# QuadWing.net
KiCad netlist of a schematic drawn in EAGLE
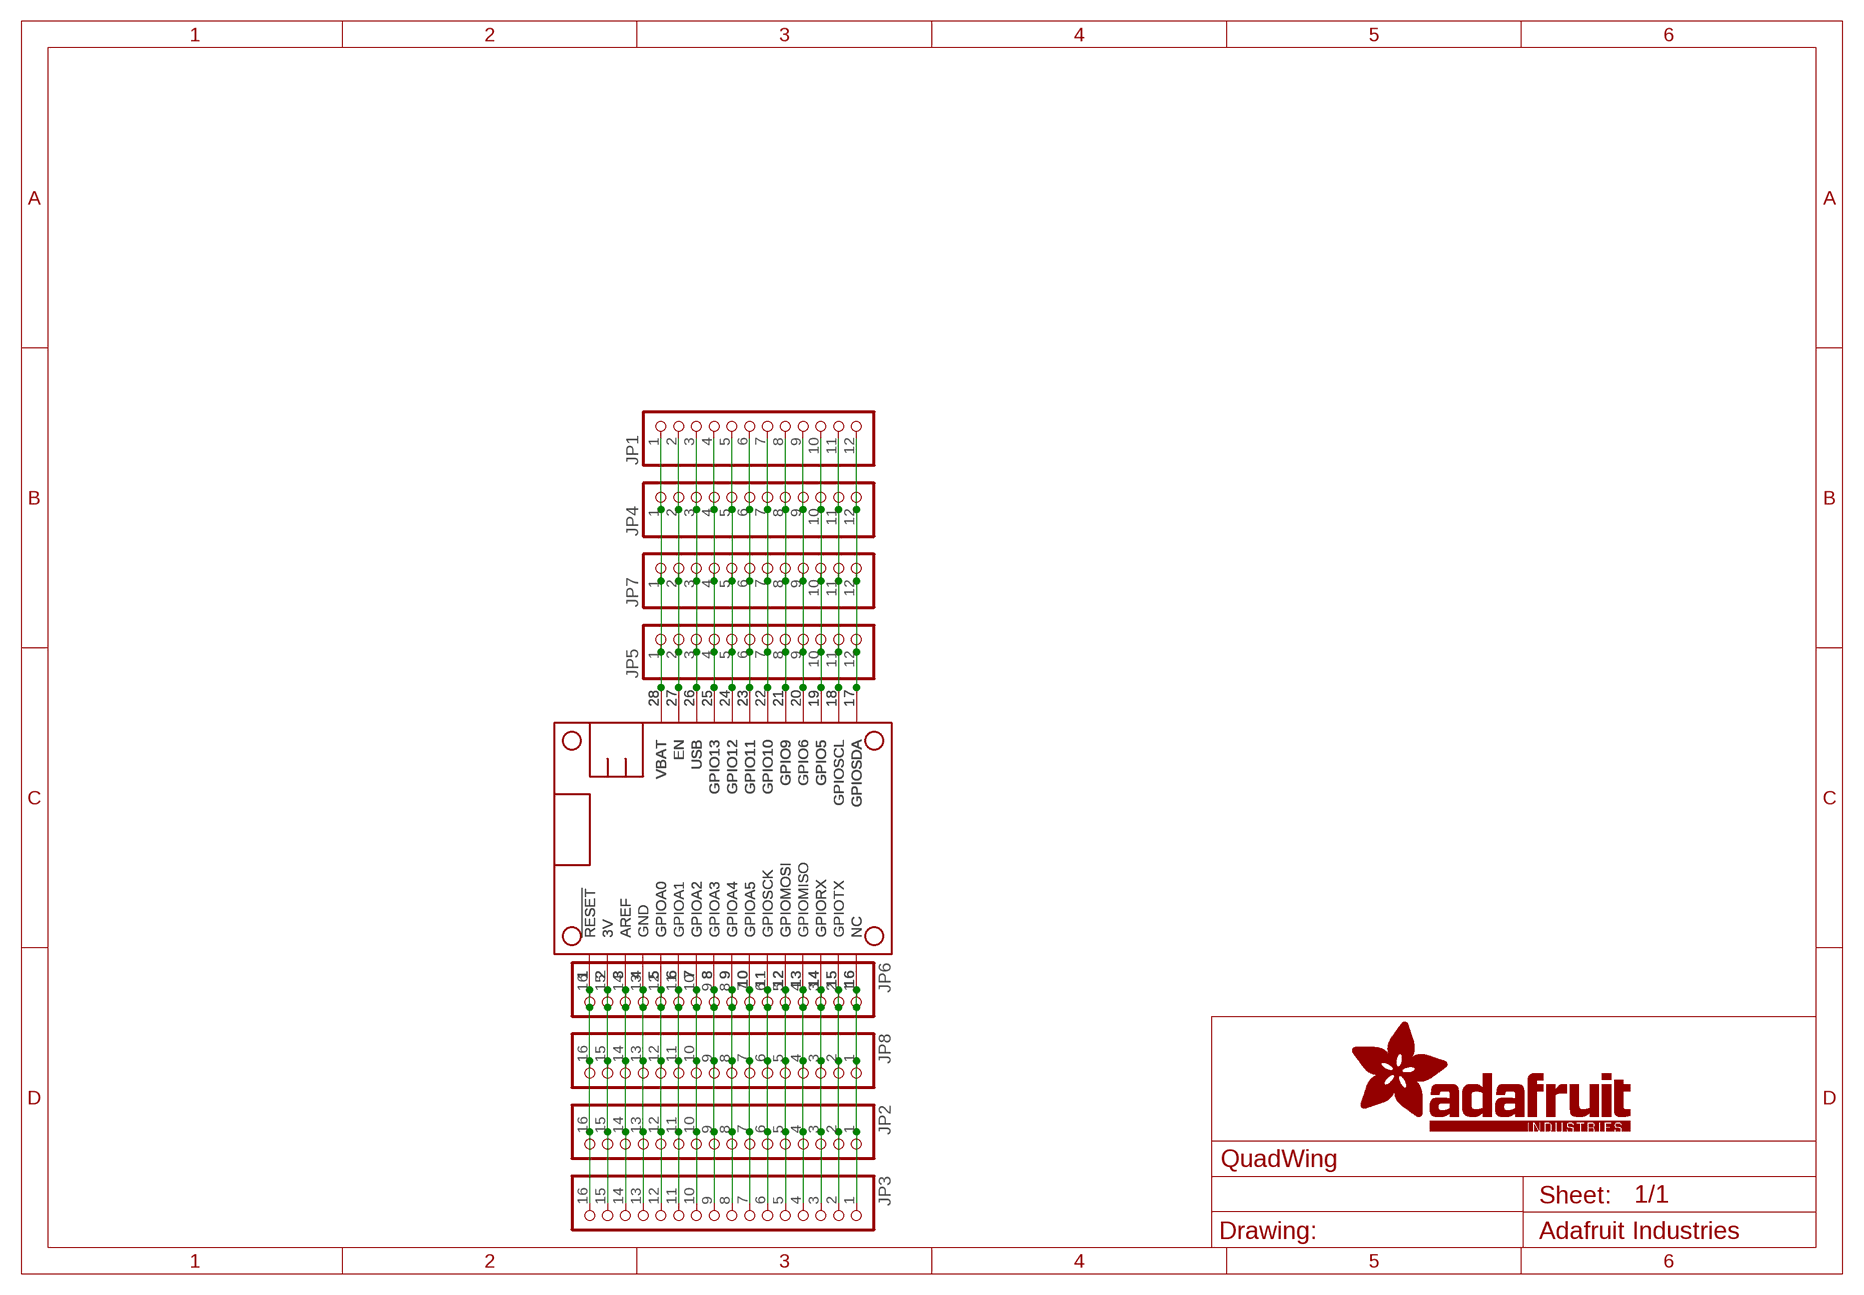
[diagram p0: schematic, sheet 1]

(export (version "E")
  (design (tool "Eeschema 10.0.6"))
  (components
    (comp (ref "JP1")
      (value "HEADER-1X1276MIL")
      (footprint "eagle-import:1X12_ROUND_76MIL")
      (libsource (lib "eagle-import") (part "HEADER-1X1276MIL"))
    )
    (comp (ref "JP2")
      (value "HEADER-1X16_76MIL")
      (footprint "eagle-import:1X16_ROUND_76MIL")
      (libsource (lib "eagle-import") (part "HEADER-1X16_76MIL"))
    )
    (comp (ref "JP3")
      (value "HEADER-1X16_76MIL")
      (footprint "eagle-import:1X16_ROUND_76MIL")
      (libsource (lib "eagle-import") (part "HEADER-1X16_76MIL"))
    )
    (comp (ref "JP4")
      (value "HEADER-1X1276MIL")
      (footprint "eagle-import:1X12_ROUND_76MIL")
      (libsource (lib "eagle-import") (part "HEADER-1X1276MIL"))
    )
    (comp (ref "JP5")
      (value "HEADER-1X1276MIL")
      (footprint "eagle-import:1X12_ROUND_76MIL")
      (libsource (lib "eagle-import") (part "HEADER-1X1276MIL"))
    )
    (comp (ref "JP6")
      (value "HEADER-1X16_76MIL")
      (footprint "eagle-import:1X16_ROUND_76MIL")
      (libsource (lib "eagle-import") (part "HEADER-1X16_76MIL"))
    )
    (comp (ref "JP7")
      (value "HEADER-1X1276MIL")
      (footprint "eagle-import:1X12_ROUND_76MIL")
      (libsource (lib "eagle-import") (part "HEADER-1X1276MIL"))
    )
    (comp (ref "JP8")
      (value "HEADER-1X16_76MIL")
      (footprint "eagle-import:1X16_ROUND_76MIL")
      (libsource (lib "eagle-import") (part "HEADER-1X16_76MIL"))
    )
    (comp (ref "MS1")
      (value "FEATHERWING_NODIM")
      (footprint "eagle-import:FEATHERWING_DIM")
      (libsource (lib "eagle-import") (part "FEATHERWING_NODIM"))
    )
    (comp (ref "MS2")
      (value "FEATHERWING_NODIM")
      (footprint "eagle-import:FEATHERWING_DIM")
      (libsource (lib "eagle-import") (part "FEATHERWING_NODIM"))
    )
    (comp (ref "MS3")
      (value "FEATHERWING_NODIM")
      (footprint "eagle-import:FEATHERWING_DIM")
      (libsource (lib "eagle-import") (part "FEATHERWING_NODIM"))
    )
    (comp (ref "MS4")
      (value "FEATHERWING_NODIM")
      (footprint "eagle-import:FEATHERWING_DIM")
      (libsource (lib "eagle-import") (part "FEATHERWING_NODIM"))
    )
  )
  (nets
    (net (code "1") (name "Net-(MS1-3V)") (class "Default")
      (node (ref "JP2") (pin "15") (pinfunction "15_15") (pintype "passive"))
      (node (ref "JP3") (pin "15") (pinfunction "15_15") (pintype "passive"))
      (node (ref "JP6") (pin "15") (pinfunction "15_15") (pintype "passive"))
      (node (ref "JP8") (pin "15") (pinfunction "15_15") (pintype "passive"))
      (node (ref "MS1") (pin "2") (pinfunction "3V_2") (pintype "power_in"))
      (node (ref "MS2") (pin "2") (pinfunction "3V_2") (pintype "power_in"))
      (node (ref "MS3") (pin "2") (pinfunction "3V_2") (pintype "power_in"))
      (node (ref "MS4") (pin "2") (pinfunction "3V_2") (pintype "power_in"))
    )
    (net (code "2") (name "Net-(MS1-AREF)") (class "Default")
      (node (ref "JP2") (pin "14") (pinfunction "14_14") (pintype "passive"))
      (node (ref "JP3") (pin "14") (pinfunction "14_14") (pintype "passive"))
      (node (ref "JP6") (pin "14") (pinfunction "14_14") (pintype "passive"))
      (node (ref "JP8") (pin "14") (pinfunction "14_14") (pintype "passive"))
      (node (ref "MS1") (pin "3") (pinfunction "AREF_3") (pintype "passive"))
      (node (ref "MS2") (pin "3") (pinfunction "AREF_3") (pintype "passive"))
      (node (ref "MS3") (pin "3") (pinfunction "AREF_3") (pintype "passive"))
      (node (ref "MS4") (pin "3") (pinfunction "AREF_3") (pintype "passive"))
    )
    (net (code "3") (name "Net-(MS1-EN)") (class "Default")
      (node (ref "JP1") (pin "2") (pinfunction "2_2") (pintype "passive"))
      (node (ref "JP4") (pin "2") (pinfunction "2_2") (pintype "passive"))
      (node (ref "JP5") (pin "2") (pinfunction "2_2") (pintype "passive"))
      (node (ref "JP7") (pin "2") (pinfunction "2_2") (pintype "passive"))
      (node (ref "MS1") (pin "27") (pinfunction "EN_27") (pintype "passive"))
      (node (ref "MS2") (pin "27") (pinfunction "EN_27") (pintype "passive"))
      (node (ref "MS3") (pin "27") (pinfunction "EN_27") (pintype "passive"))
      (node (ref "MS4") (pin "27") (pinfunction "EN_27") (pintype "passive"))
    )
    (net (code "4") (name "Net-(MS1-GND)") (class "Default")
      (node (ref "JP2") (pin "13") (pinfunction "13_13") (pintype "passive"))
      (node (ref "JP3") (pin "13") (pinfunction "13_13") (pintype "passive"))
      (node (ref "JP6") (pin "13") (pinfunction "13_13") (pintype "passive"))
      (node (ref "JP8") (pin "13") (pinfunction "13_13") (pintype "passive"))
      (node (ref "MS1") (pin "4") (pinfunction "GND_4") (pintype "power_in"))
      (node (ref "MS2") (pin "4") (pinfunction "GND_4") (pintype "power_in"))
      (node (ref "MS3") (pin "4") (pinfunction "GND_4") (pintype "power_in"))
      (node (ref "MS4") (pin "4") (pinfunction "GND_4") (pintype "power_in"))
    )
    (net (code "5") (name "Net-(MS1-GPIO5)") (class "Default")
      (node (ref "JP1") (pin "10") (pinfunction "10_10") (pintype "passive"))
      (node (ref "JP4") (pin "10") (pinfunction "10_10") (pintype "passive"))
      (node (ref "JP5") (pin "10") (pinfunction "10_10") (pintype "passive"))
      (node (ref "JP7") (pin "10") (pinfunction "10_10") (pintype "passive"))
      (node (ref "MS1") (pin "19") (pinfunction "GPIO5_19") (pintype "bidirectional"))
      (node (ref "MS2") (pin "19") (pinfunction "GPIO5_19") (pintype "bidirectional"))
      (node (ref "MS3") (pin "19") (pinfunction "GPIO5_19") (pintype "bidirectional"))
      (node (ref "MS4") (pin "19") (pinfunction "GPIO5_19") (pintype "bidirectional"))
    )
    (net (code "6") (name "Net-(MS1-GPIO6)") (class "Default")
      (node (ref "JP1") (pin "9") (pinfunction "9_9") (pintype "passive"))
      (node (ref "JP4") (pin "9") (pinfunction "9_9") (pintype "passive"))
      (node (ref "JP5") (pin "9") (pinfunction "9_9") (pintype "passive"))
      (node (ref "JP7") (pin "9") (pinfunction "9_9") (pintype "passive"))
      (node (ref "MS1") (pin "20") (pinfunction "GPIO6_20") (pintype "bidirectional"))
      (node (ref "MS2") (pin "20") (pinfunction "GPIO6_20") (pintype "bidirectional"))
      (node (ref "MS3") (pin "20") (pinfunction "GPIO6_20") (pintype "bidirectional"))
      (node (ref "MS4") (pin "20") (pinfunction "GPIO6_20") (pintype "bidirectional"))
    )
    (net (code "7") (name "Net-(MS1-GPIO9)") (class "Default")
      (node (ref "JP1") (pin "8") (pinfunction "8_8") (pintype "passive"))
      (node (ref "JP4") (pin "8") (pinfunction "8_8") (pintype "passive"))
      (node (ref "JP5") (pin "8") (pinfunction "8_8") (pintype "passive"))
      (node (ref "JP7") (pin "8") (pinfunction "8_8") (pintype "passive"))
      (node (ref "MS1") (pin "21") (pinfunction "GPIO9_21") (pintype "bidirectional"))
      (node (ref "MS2") (pin "21") (pinfunction "GPIO9_21") (pintype "bidirectional"))
      (node (ref "MS3") (pin "21") (pinfunction "GPIO9_21") (pintype "bidirectional"))
      (node (ref "MS4") (pin "21") (pinfunction "GPIO9_21") (pintype "bidirectional"))
    )
    (net (code "8") (name "Net-(MS1-GPIO10)") (class "Default")
      (node (ref "JP1") (pin "7") (pinfunction "7_7") (pintype "passive"))
      (node (ref "JP4") (pin "7") (pinfunction "7_7") (pintype "passive"))
      (node (ref "JP5") (pin "7") (pinfunction "7_7") (pintype "passive"))
      (node (ref "JP7") (pin "7") (pinfunction "7_7") (pintype "passive"))
      (node (ref "MS1") (pin "22") (pinfunction "GPIO10_22") (pintype "bidirectional"))
      (node (ref "MS2") (pin "22") (pinfunction "GPIO10_22") (pintype "bidirectional"))
      (node (ref "MS3") (pin "22") (pinfunction "GPIO10_22") (pintype "bidirectional"))
      (node (ref "MS4") (pin "22") (pinfunction "GPIO10_22") (pintype "bidirectional"))
    )
    (net (code "9") (name "Net-(MS1-GPIO11)") (class "Default")
      (node (ref "JP1") (pin "6") (pinfunction "6_6") (pintype "passive"))
      (node (ref "JP4") (pin "6") (pinfunction "6_6") (pintype "passive"))
      (node (ref "JP5") (pin "6") (pinfunction "6_6") (pintype "passive"))
      (node (ref "JP7") (pin "6") (pinfunction "6_6") (pintype "passive"))
      (node (ref "MS1") (pin "23") (pinfunction "GPIO11_23") (pintype "bidirectional"))
      (node (ref "MS2") (pin "23") (pinfunction "GPIO11_23") (pintype "bidirectional"))
      (node (ref "MS3") (pin "23") (pinfunction "GPIO11_23") (pintype "bidirectional"))
      (node (ref "MS4") (pin "23") (pinfunction "GPIO11_23") (pintype "bidirectional"))
    )
    (net (code "10") (name "Net-(MS1-GPIO12)") (class "Default")
      (node (ref "JP1") (pin "5") (pinfunction "5_5") (pintype "passive"))
      (node (ref "JP4") (pin "5") (pinfunction "5_5") (pintype "passive"))
      (node (ref "JP5") (pin "5") (pinfunction "5_5") (pintype "passive"))
      (node (ref "JP7") (pin "5") (pinfunction "5_5") (pintype "passive"))
      (node (ref "MS1") (pin "24") (pinfunction "GPIO12_24") (pintype "bidirectional"))
      (node (ref "MS2") (pin "24") (pinfunction "GPIO12_24") (pintype "bidirectional"))
      (node (ref "MS3") (pin "24") (pinfunction "GPIO12_24") (pintype "bidirectional"))
      (node (ref "MS4") (pin "24") (pinfunction "GPIO12_24") (pintype "bidirectional"))
    )
    (net (code "11") (name "Net-(MS1-GPIO13)") (class "Default")
      (node (ref "JP1") (pin "4") (pinfunction "4_4") (pintype "passive"))
      (node (ref "JP4") (pin "4") (pinfunction "4_4") (pintype "passive"))
      (node (ref "JP5") (pin "4") (pinfunction "4_4") (pintype "passive"))
      (node (ref "JP7") (pin "4") (pinfunction "4_4") (pintype "passive"))
      (node (ref "MS1") (pin "25") (pinfunction "GPIO13_25") (pintype "bidirectional"))
      (node (ref "MS2") (pin "25") (pinfunction "GPIO13_25") (pintype "bidirectional"))
      (node (ref "MS3") (pin "25") (pinfunction "GPIO13_25") (pintype "bidirectional"))
      (node (ref "MS4") (pin "25") (pinfunction "GPIO13_25") (pintype "bidirectional"))
    )
    (net (code "12") (name "Net-(MS1-GPIOA0)") (class "Default")
      (node (ref "JP2") (pin "12") (pinfunction "12_12") (pintype "passive"))
      (node (ref "JP3") (pin "12") (pinfunction "12_12") (pintype "passive"))
      (node (ref "JP6") (pin "12") (pinfunction "12_12") (pintype "passive"))
      (node (ref "JP8") (pin "12") (pinfunction "12_12") (pintype "passive"))
      (node (ref "MS1") (pin "5") (pinfunction "GPIOA0_5") (pintype "bidirectional"))
      (node (ref "MS2") (pin "5") (pinfunction "GPIOA0_5") (pintype "bidirectional"))
      (node (ref "MS3") (pin "5") (pinfunction "GPIOA0_5") (pintype "bidirectional"))
      (node (ref "MS4") (pin "5") (pinfunction "GPIOA0_5") (pintype "bidirectional"))
    )
    (net (code "13") (name "Net-(MS1-GPIOA1)") (class "Default")
      (node (ref "JP2") (pin "11") (pinfunction "11_11") (pintype "passive"))
      (node (ref "JP3") (pin "11") (pinfunction "11_11") (pintype "passive"))
      (node (ref "JP6") (pin "11") (pinfunction "11_11") (pintype "passive"))
      (node (ref "JP8") (pin "11") (pinfunction "11_11") (pintype "passive"))
      (node (ref "MS1") (pin "6") (pinfunction "GPIOA1_6") (pintype "bidirectional"))
      (node (ref "MS2") (pin "6") (pinfunction "GPIOA1_6") (pintype "bidirectional"))
      (node (ref "MS3") (pin "6") (pinfunction "GPIOA1_6") (pintype "bidirectional"))
      (node (ref "MS4") (pin "6") (pinfunction "GPIOA1_6") (pintype "bidirectional"))
    )
    (net (code "14") (name "Net-(MS1-GPIOA2)") (class "Default")
      (node (ref "JP2") (pin "10") (pinfunction "10_10") (pintype "passive"))
      (node (ref "JP3") (pin "10") (pinfunction "10_10") (pintype "passive"))
      (node (ref "JP6") (pin "10") (pinfunction "10_10") (pintype "passive"))
      (node (ref "JP8") (pin "10") (pinfunction "10_10") (pintype "passive"))
      (node (ref "MS1") (pin "7") (pinfunction "GPIOA2_7") (pintype "bidirectional"))
      (node (ref "MS2") (pin "7") (pinfunction "GPIOA2_7") (pintype "bidirectional"))
      (node (ref "MS3") (pin "7") (pinfunction "GPIOA2_7") (pintype "bidirectional"))
      (node (ref "MS4") (pin "7") (pinfunction "GPIOA2_7") (pintype "bidirectional"))
    )
    (net (code "15") (name "Net-(MS1-GPIOA3)") (class "Default")
      (node (ref "JP2") (pin "9") (pinfunction "9_9") (pintype "passive"))
      (node (ref "JP3") (pin "9") (pinfunction "9_9") (pintype "passive"))
      (node (ref "JP6") (pin "9") (pinfunction "9_9") (pintype "passive"))
      (node (ref "JP8") (pin "9") (pinfunction "9_9") (pintype "passive"))
      (node (ref "MS1") (pin "8") (pinfunction "GPIOA3_8") (pintype "bidirectional"))
      (node (ref "MS2") (pin "8") (pinfunction "GPIOA3_8") (pintype "bidirectional"))
      (node (ref "MS3") (pin "8") (pinfunction "GPIOA3_8") (pintype "bidirectional"))
      (node (ref "MS4") (pin "8") (pinfunction "GPIOA3_8") (pintype "bidirectional"))
    )
    (net (code "16") (name "Net-(MS1-GPIOA4)") (class "Default")
      (node (ref "JP2") (pin "8") (pinfunction "8_8") (pintype "passive"))
      (node (ref "JP3") (pin "8") (pinfunction "8_8") (pintype "passive"))
      (node (ref "JP6") (pin "8") (pinfunction "8_8") (pintype "passive"))
      (node (ref "JP8") (pin "8") (pinfunction "8_8") (pintype "passive"))
      (node (ref "MS1") (pin "9") (pinfunction "GPIOA4_9") (pintype "bidirectional"))
      (node (ref "MS2") (pin "9") (pinfunction "GPIOA4_9") (pintype "bidirectional"))
      (node (ref "MS3") (pin "9") (pinfunction "GPIOA4_9") (pintype "bidirectional"))
      (node (ref "MS4") (pin "9") (pinfunction "GPIOA4_9") (pintype "bidirectional"))
    )
    (net (code "17") (name "Net-(MS1-GPIOA5)") (class "Default")
      (node (ref "JP2") (pin "7") (pinfunction "7_7") (pintype "passive"))
      (node (ref "JP3") (pin "7") (pinfunction "7_7") (pintype "passive"))
      (node (ref "JP6") (pin "7") (pinfunction "7_7") (pintype "passive"))
      (node (ref "JP8") (pin "7") (pinfunction "7_7") (pintype "passive"))
      (node (ref "MS1") (pin "10") (pinfunction "GPIOA5_10") (pintype "bidirectional"))
      (node (ref "MS2") (pin "10") (pinfunction "GPIOA5_10") (pintype "bidirectional"))
      (node (ref "MS3") (pin "10") (pinfunction "GPIOA5_10") (pintype "bidirectional"))
      (node (ref "MS4") (pin "10") (pinfunction "GPIOA5_10") (pintype "bidirectional"))
    )
    (net (code "18") (name "Net-(MS1-GPIOMISO)") (class "Default")
      (node (ref "JP2") (pin "4") (pinfunction "4_4") (pintype "passive"))
      (node (ref "JP3") (pin "4") (pinfunction "4_4") (pintype "passive"))
      (node (ref "JP6") (pin "4") (pinfunction "4_4") (pintype "passive"))
      (node (ref "JP8") (pin "4") (pinfunction "4_4") (pintype "passive"))
      (node (ref "MS1") (pin "13") (pinfunction "GPIOMISO_13") (pintype "bidirectional"))
      (node (ref "MS2") (pin "13") (pinfunction "GPIOMISO_13") (pintype "bidirectional"))
      (node (ref "MS3") (pin "13") (pinfunction "GPIOMISO_13") (pintype "bidirectional"))
      (node (ref "MS4") (pin "13") (pinfunction "GPIOMISO_13") (pintype "bidirectional"))
    )
    (net (code "19") (name "Net-(MS1-GPIOMOSI)") (class "Default")
      (node (ref "JP2") (pin "5") (pinfunction "5_5") (pintype "passive"))
      (node (ref "JP3") (pin "5") (pinfunction "5_5") (pintype "passive"))
      (node (ref "JP6") (pin "5") (pinfunction "5_5") (pintype "passive"))
      (node (ref "JP8") (pin "5") (pinfunction "5_5") (pintype "passive"))
      (node (ref "MS1") (pin "12") (pinfunction "GPIOMOSI_12") (pintype "bidirectional"))
      (node (ref "MS2") (pin "12") (pinfunction "GPIOMOSI_12") (pintype "bidirectional"))
      (node (ref "MS3") (pin "12") (pinfunction "GPIOMOSI_12") (pintype "bidirectional"))
      (node (ref "MS4") (pin "12") (pinfunction "GPIOMOSI_12") (pintype "bidirectional"))
    )
    (net (code "20") (name "Net-(MS1-GPIORX)") (class "Default")
      (node (ref "JP2") (pin "3") (pinfunction "3_3") (pintype "passive"))
      (node (ref "JP3") (pin "3") (pinfunction "3_3") (pintype "passive"))
      (node (ref "JP6") (pin "3") (pinfunction "3_3") (pintype "passive"))
      (node (ref "JP8") (pin "3") (pinfunction "3_3") (pintype "passive"))
      (node (ref "MS1") (pin "14") (pinfunction "GPIORX_14") (pintype "bidirectional"))
      (node (ref "MS2") (pin "14") (pinfunction "GPIORX_14") (pintype "bidirectional"))
      (node (ref "MS3") (pin "14") (pinfunction "GPIORX_14") (pintype "bidirectional"))
      (node (ref "MS4") (pin "14") (pinfunction "GPIORX_14") (pintype "bidirectional"))
    )
    (net (code "21") (name "Net-(MS1-GPIOSCK)") (class "Default")
      (node (ref "JP2") (pin "6") (pinfunction "6_6") (pintype "passive"))
      (node (ref "JP3") (pin "6") (pinfunction "6_6") (pintype "passive"))
      (node (ref "JP6") (pin "6") (pinfunction "6_6") (pintype "passive"))
      (node (ref "JP8") (pin "6") (pinfunction "6_6") (pintype "passive"))
      (node (ref "MS1") (pin "11") (pinfunction "GPIOSCK_11") (pintype "bidirectional"))
      (node (ref "MS2") (pin "11") (pinfunction "GPIOSCK_11") (pintype "bidirectional"))
      (node (ref "MS3") (pin "11") (pinfunction "GPIOSCK_11") (pintype "bidirectional"))
      (node (ref "MS4") (pin "11") (pinfunction "GPIOSCK_11") (pintype "bidirectional"))
    )
    (net (code "22") (name "Net-(MS1-GPIOSCL)") (class "Default")
      (node (ref "JP1") (pin "11") (pinfunction "11_11") (pintype "passive"))
      (node (ref "JP4") (pin "11") (pinfunction "11_11") (pintype "passive"))
      (node (ref "JP5") (pin "11") (pinfunction "11_11") (pintype "passive"))
      (node (ref "JP7") (pin "11") (pinfunction "11_11") (pintype "passive"))
      (node (ref "MS1") (pin "18") (pinfunction "GPIOSCL_18") (pintype "bidirectional"))
      (node (ref "MS2") (pin "18") (pinfunction "GPIOSCL_18") (pintype "bidirectional"))
      (node (ref "MS3") (pin "18") (pinfunction "GPIOSCL_18") (pintype "bidirectional"))
      (node (ref "MS4") (pin "18") (pinfunction "GPIOSCL_18") (pintype "bidirectional"))
    )
    (net (code "23") (name "Net-(MS1-GPIOSDA)") (class "Default")
      (node (ref "JP1") (pin "12") (pinfunction "12_12") (pintype "passive"))
      (node (ref "JP4") (pin "12") (pinfunction "12_12") (pintype "passive"))
      (node (ref "JP5") (pin "12") (pinfunction "12_12") (pintype "passive"))
      (node (ref "JP7") (pin "12") (pinfunction "12_12") (pintype "passive"))
      (node (ref "MS1") (pin "17") (pinfunction "GPIOSDA_17") (pintype "bidirectional"))
      (node (ref "MS2") (pin "17") (pinfunction "GPIOSDA_17") (pintype "bidirectional"))
      (node (ref "MS3") (pin "17") (pinfunction "GPIOSDA_17") (pintype "bidirectional"))
      (node (ref "MS4") (pin "17") (pinfunction "GPIOSDA_17") (pintype "bidirectional"))
    )
    (net (code "24") (name "Net-(MS1-GPIOTX)") (class "Default")
      (node (ref "JP2") (pin "2") (pinfunction "2_2") (pintype "passive"))
      (node (ref "JP3") (pin "2") (pinfunction "2_2") (pintype "passive"))
      (node (ref "JP6") (pin "2") (pinfunction "2_2") (pintype "passive"))
      (node (ref "JP8") (pin "2") (pinfunction "2_2") (pintype "passive"))
      (node (ref "MS1") (pin "15") (pinfunction "GPIOTX_15") (pintype "bidirectional"))
      (node (ref "MS2") (pin "15") (pinfunction "GPIOTX_15") (pintype "bidirectional"))
      (node (ref "MS3") (pin "15") (pinfunction "GPIOTX_15") (pintype "bidirectional"))
      (node (ref "MS4") (pin "15") (pinfunction "GPIOTX_15") (pintype "bidirectional"))
    )
    (net (code "25") (name "Net-(MS1-NC)") (class "Default")
      (node (ref "JP2") (pin "1") (pinfunction "1_1") (pintype "passive"))
      (node (ref "JP3") (pin "1") (pinfunction "1_1") (pintype "passive"))
      (node (ref "JP6") (pin "1") (pinfunction "1_1") (pintype "passive"))
      (node (ref "JP8") (pin "1") (pinfunction "1_1") (pintype "passive"))
      (node (ref "MS1") (pin "16") (pinfunction "NC_16") (pintype "passive"))
      (node (ref "MS2") (pin "16") (pinfunction "NC_16") (pintype "passive"))
      (node (ref "MS3") (pin "16") (pinfunction "NC_16") (pintype "passive"))
      (node (ref "MS4") (pin "16") (pinfunction "NC_16") (pintype "passive"))
    )
    (net (code "26") (name "Net-(MS1-USB)") (class "Default")
      (node (ref "JP1") (pin "3") (pinfunction "3_3") (pintype "passive"))
      (node (ref "JP4") (pin "3") (pinfunction "3_3") (pintype "passive"))
      (node (ref "JP5") (pin "3") (pinfunction "3_3") (pintype "passive"))
      (node (ref "JP7") (pin "3") (pinfunction "3_3") (pintype "passive"))
      (node (ref "MS1") (pin "26") (pinfunction "USB_26") (pintype "power_in"))
      (node (ref "MS2") (pin "26") (pinfunction "USB_26") (pintype "power_in"))
      (node (ref "MS3") (pin "26") (pinfunction "USB_26") (pintype "power_in"))
      (node (ref "MS4") (pin "26") (pinfunction "USB_26") (pintype "power_in"))
    )
    (net (code "27") (name "Net-(MS1-VBAT)") (class "Default")
      (node (ref "JP1") (pin "1") (pinfunction "1_1") (pintype "passive"))
      (node (ref "JP4") (pin "1") (pinfunction "1_1") (pintype "passive"))
      (node (ref "JP5") (pin "1") (pinfunction "1_1") (pintype "passive"))
      (node (ref "JP7") (pin "1") (pinfunction "1_1") (pintype "passive"))
      (node (ref "MS1") (pin "28") (pinfunction "VBAT_28") (pintype "power_in"))
      (node (ref "MS2") (pin "28") (pinfunction "VBAT_28") (pintype "power_in"))
      (node (ref "MS3") (pin "28") (pinfunction "VBAT_28") (pintype "power_in"))
      (node (ref "MS4") (pin "28") (pinfunction "VBAT_28") (pintype "power_in"))
    )
    (net (code "28") (name "Net-(MS1-~{RESET})") (class "Default")
      (node (ref "JP2") (pin "16") (pinfunction "16_16") (pintype "passive"))
      (node (ref "JP3") (pin "16") (pinfunction "16_16") (pintype "passive"))
      (node (ref "JP6") (pin "16") (pinfunction "16_16") (pintype "passive"))
      (node (ref "JP8") (pin "16") (pinfunction "16_16") (pintype "passive"))
      (node (ref "MS1") (pin "1") (pinfunction "~{RESET}_1") (pintype "input"))
      (node (ref "MS2") (pin "1") (pinfunction "~{RESET}_1") (pintype "input"))
      (node (ref "MS3") (pin "1") (pinfunction "~{RESET}_1") (pintype "input"))
      (node (ref "MS4") (pin "1") (pinfunction "~{RESET}_1") (pintype "input"))
    )
  )
)
